# USB2CAN.net
KiCad netlist of a schematic drawn in Altium Designer
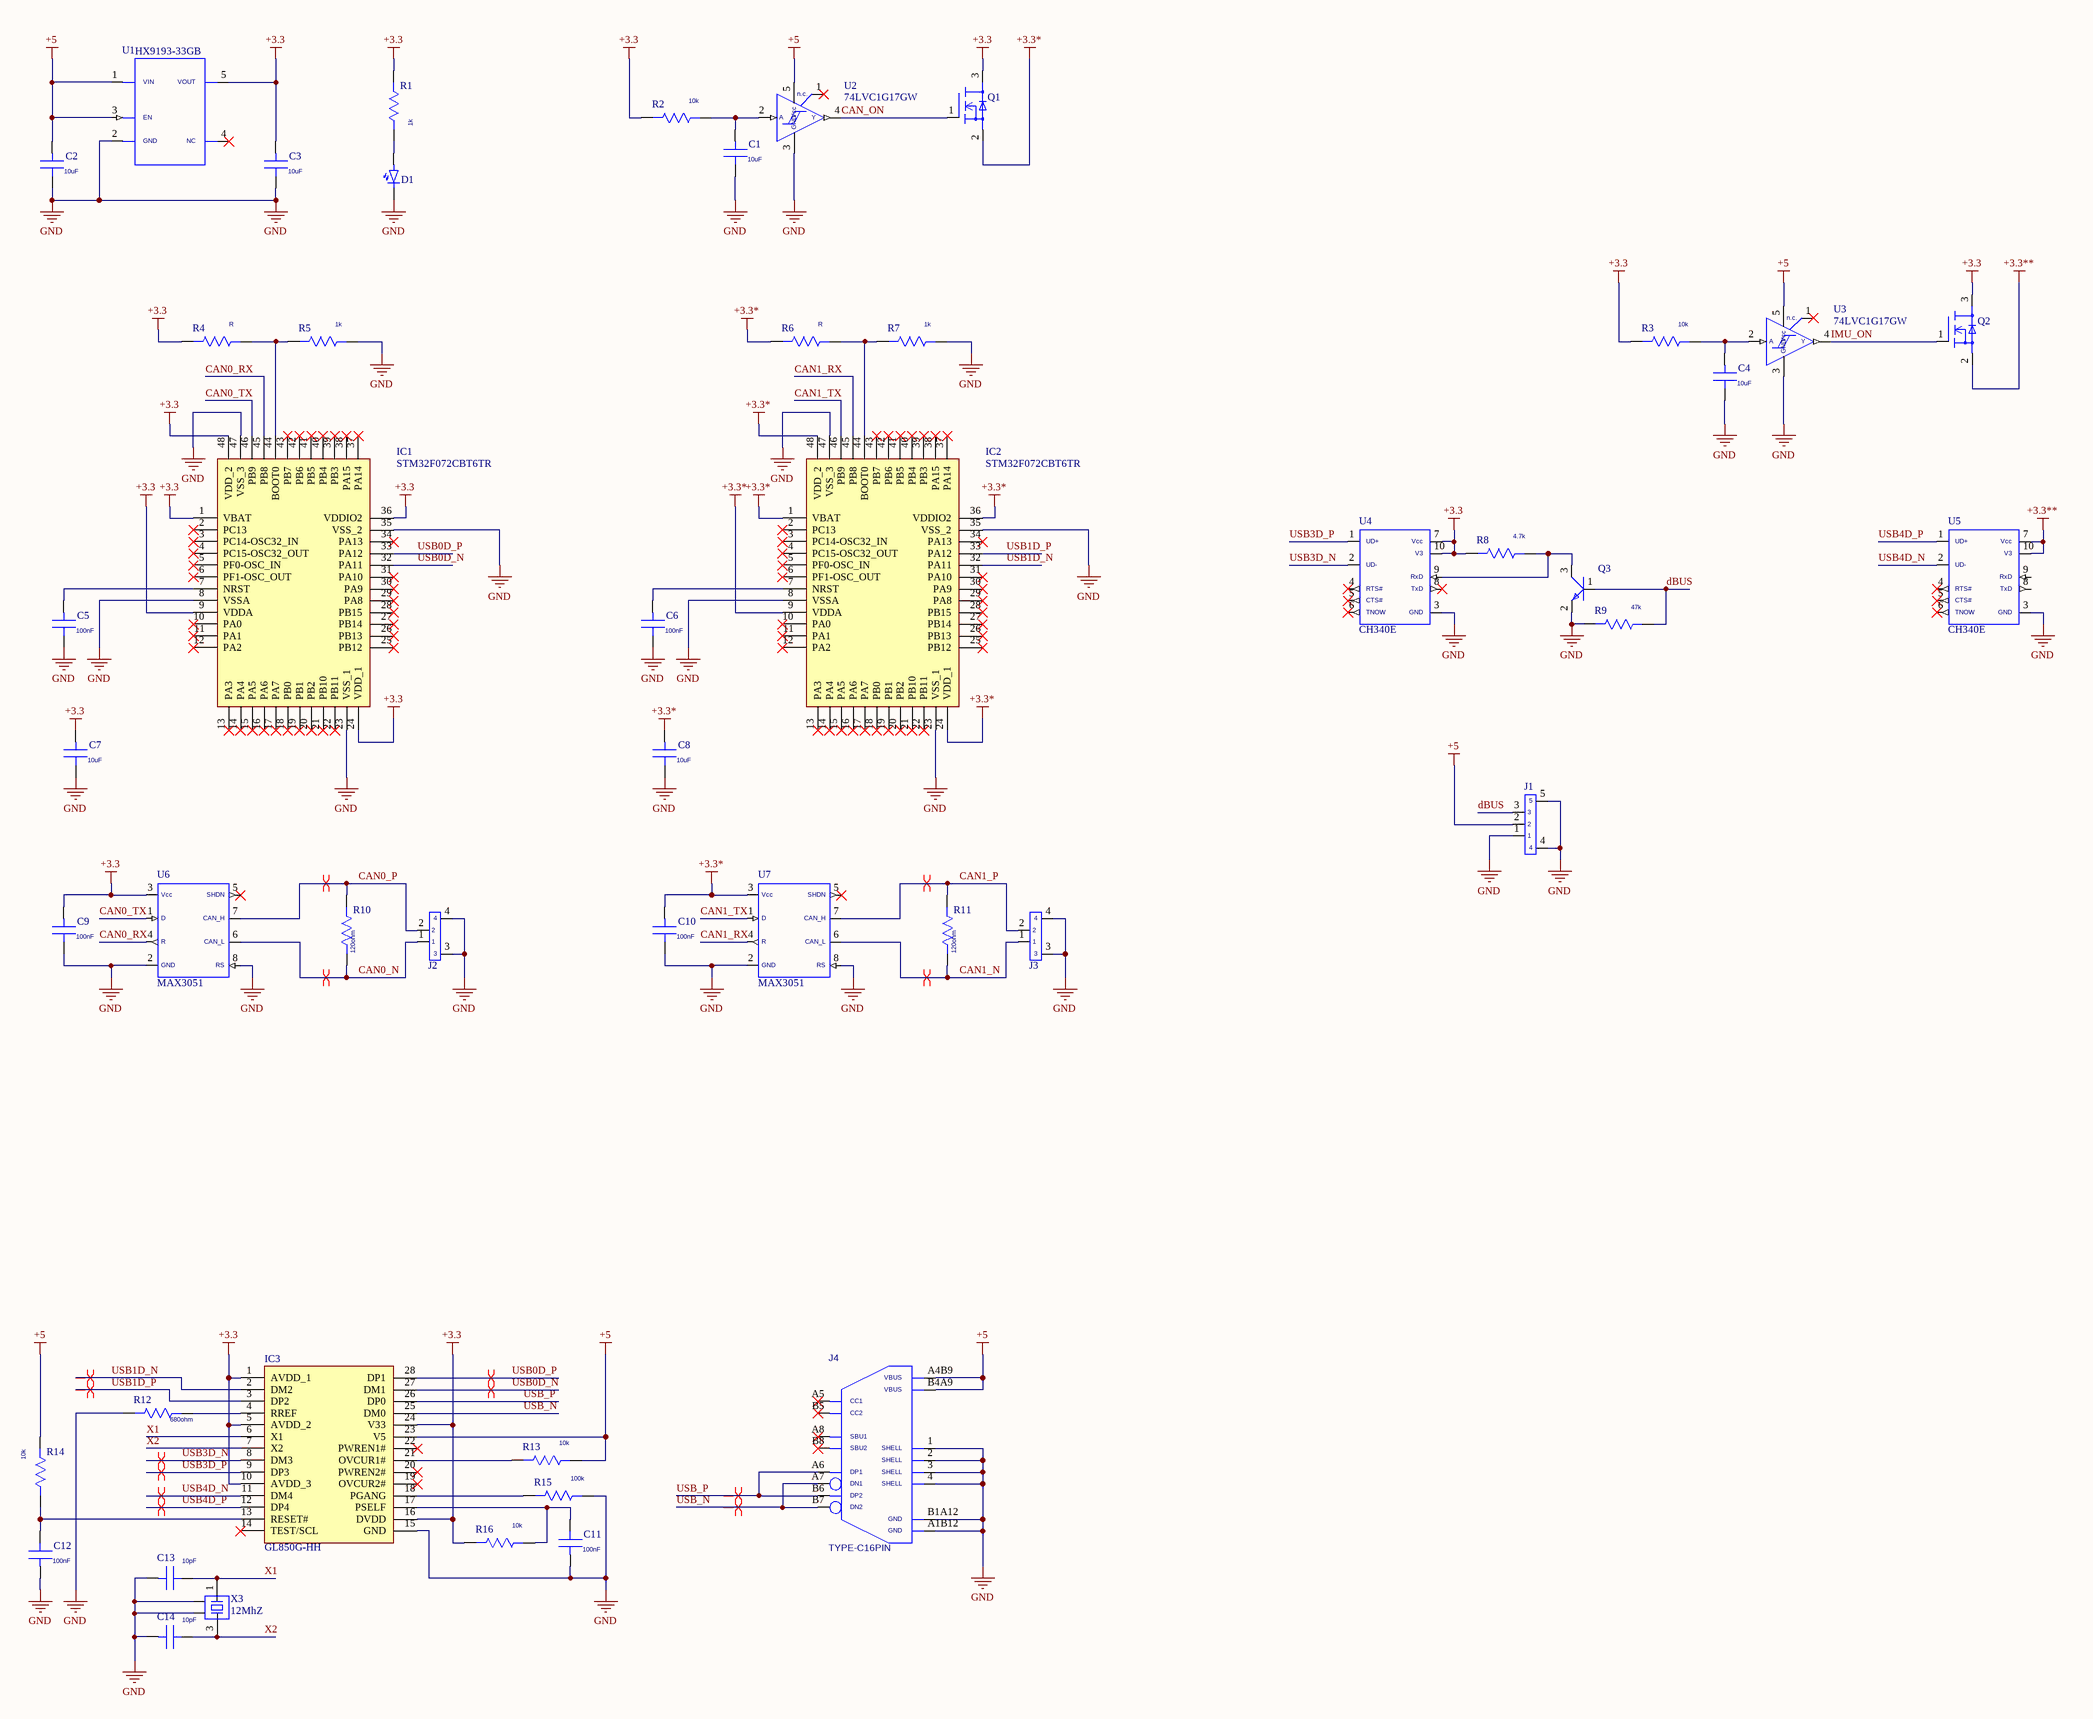
[diagram p0: USB2CAN.SchDoc]

(export (version "E")
  (design (tool "Eeschema 10.0.6"))
  (components
    (comp (ref "C1") (value "10uF") (footprint "0603C(M1608C)") (libsource (lib "ADlib @LAN") (part "C")))
    (comp (ref "C2") (value "10uF") (footprint "0603C(M1608C)") (libsource (lib "ADlib @LAN") (part "C")))
    (comp (ref "C3") (value "10uF") (footprint "0603C(M1608C)") (libsource (lib "ADlib @LAN") (part "C")))
    (comp (ref "C4") (value "10uF") (footprint "0603C(M1608C)") (libsource (lib "ADlib @LAN") (part "C")))
    (comp (ref "C5") (value "100nF") (footprint "0402C(M1005C)") (libsource (lib "ADlib @LAN") (part "C")))
    (comp (ref "C6") (value "100nF") (footprint "0402C(M1005C)") (libsource (lib "ADlib @LAN") (part "C")))
    (comp (ref "C7") (value "10uF") (footprint "0603C(M1608C)") (libsource (lib "ADlib @LAN") (part "C")))
    (comp (ref "C8") (value "10uF") (footprint "0603C(M1608C)") (libsource (lib "ADlib @LAN") (part "C")))
    (comp (ref "C9") (value "100nF") (footprint "0402C(M1005C)") (libsource (lib "ADlib @LAN") (part "C")))
    (comp (ref "C10") (value "100nF") (footprint "0402C(M1005C)") (libsource (lib "ADlib @LAN") (part "C")))
    (comp (ref "C11") (value "100nF") (footprint "0402C(M1005C)") (libsource (lib "ADlib @LAN") (part "C")))
    (comp (ref "C12") (value "100nF") (footprint "0402C(M1005C)") (libsource (lib "ADlib @LAN") (part "C")))
    (comp (ref "C13") (value "10pF") (footprint "0402C(M1005C)") (libsource (lib "ADlib @LAN") (part "C")))
    (comp (ref "C14") (value "10pF") (footprint "0402C(M1005C)") (libsource (lib "ADlib @LAN") (part "C")))
    (comp (ref "D1") (value "LED") (footprint "LED0603") (libsource (lib "ADlib @LAN") (part "LED")))
    (comp (ref "IC1")
      (value "STM32F072CBT6TR")
      (footprint "SamacSys:QFP50P900X900X160-48N")
      (description "Integrated Circuit")
      (fields
        (field (name "MOUSER PART NUMBER") "511-STM32F072CBT6TR")
        (field (name "RS PART NUMBER") "1923612")
      )
      (libsource (lib "*") (part "STM32F072CBT6TR"))
    )
    (comp (ref "IC2")
      (value "STM32F072CBT6TR")
      (footprint "SamacSys:QFP50P900X900X160-48N")
      (description "Integrated Circuit")
      (fields
        (field (name "MOUSER PART NUMBER") "511-STM32F072CBT6TR")
        (field (name "RS PART NUMBER") "1923612")
      )
      (libsource (lib "*") (part "STM32F072CBT6TR"))
    )
    (comp (ref "IC3")
      (value "GL850G-HH")
      (footprint "SamacSys:SOP65P780X200-28N")
      (description "Integrated Circuit")
      (libsource (lib "*") (part "GL850G-HH"))
    )
    (comp (ref "J1")
      (value "X1251WRS-03HF-LPSW")
      (footprint "GH1.25-3P")
      (libsource (lib "ADlib @LAN") (part "CON_GH1.25_3P"))
    )
    (comp (ref "J2")
      (value "X1251WRS-02HF-LPSW")
      (footprint "GH1.25-2P")
      (libsource (lib "ADlib @LAN") (part "CON_GH1.25_2P"))
    )
    (comp (ref "J3")
      (value "X1251WRS-02HF-LPSW")
      (footprint "GH1.25-2P")
      (libsource (lib "ADlib @LAN") (part "CON_GH1.25_2P"))
    )
    (comp (ref "J4")
      (value "TYPE-C16PIN")
      (footprint "Type-C 16P")
      (fields (field (name "BOM_SUPPLIER PART") "C393939") (field (name "CONTRIBUTOR") "LCSC"))
      (libsource (lib "ADlib @LAN") (part "CON_USB3#1"))
    )
    (comp (ref "Q1") (value "Q_FET_N") (footprint "SOT23") (libsource (lib "ADlib @LAN") (part "Q_FET_N")))
    (comp (ref "Q2") (value "Q_FET_N") (footprint "SOT23") (libsource (lib "ADlib @LAN") (part "Q_FET_N")))
    (comp (ref "Q3")
      (value "Q_NPN")
      (footprint "ADlib @LAN:SOT23")
      (libsource (lib "ADlib @LAN") (part "Q_NPN"))
    )
    (comp (ref "R1") (value "1k") (footprint "0402R") (libsource (lib "ADlib @LAN") (part "R")))
    (comp (ref "R2") (value "10k") (footprint "0402R") (libsource (lib "ADlib @LAN") (part "R")))
    (comp (ref "R3") (value "10k") (footprint "0402R") (libsource (lib "ADlib @LAN") (part "R")))
    (comp (ref "R4") (value "R") (footprint "0402R") (libsource (lib "ADlib @LAN") (part "R")))
    (comp (ref "R5") (value "1k") (footprint "0402R") (libsource (lib "ADlib @LAN") (part "R")))
    (comp (ref "R6") (value "R") (footprint "0402R") (libsource (lib "ADlib @LAN") (part "R")))
    (comp (ref "R7") (value "1k") (footprint "0402R") (libsource (lib "ADlib @LAN") (part "R")))
    (comp (ref "R8") (value "4.7k") (footprint "0402R") (libsource (lib "ADlib @LAN") (part "R")))
    (comp (ref "R9") (value "47k") (footprint "0402R") (libsource (lib "ADlib @LAN") (part "R")))
    (comp (ref "R10") (value "120ohm") (footprint "0402R") (libsource (lib "ADlib @LAN") (part "R")))
    (comp (ref "R11") (value "120ohm") (footprint "0402R") (libsource (lib "ADlib @LAN") (part "R")))
    (comp (ref "R12") (value "680ohm") (footprint "0402R") (libsource (lib "ADlib @LAN") (part "R")))
    (comp (ref "R13") (value "10k") (footprint "0402R") (libsource (lib "ADlib @LAN") (part "R")))
    (comp (ref "R14") (value "10k") (footprint "0402R") (libsource (lib "ADlib @LAN") (part "R")))
    (comp (ref "R15") (value "100k") (footprint "0402R") (libsource (lib "ADlib @LAN") (part "R")))
    (comp (ref "R16") (value "10k") (footprint "0402R") (libsource (lib "ADlib @LAN") (part "R")))
    (comp (ref "U1")
      (value "HX9193-33GB")
      (footprint "ADlib @LAN:SOT23_5")
      (libsource (lib "ADlib @LAN") (part "U_LDO"))
    )
    (comp (ref "U2")
      (value "74LVC1G17GW")
      (footprint "SOT353")
      (libsource (lib "ADlib @LAN") (part "U_Schmitt"))
    )
    (comp (ref "U3")
      (value "74LVC1G17GW")
      (footprint "SOT353")
      (libsource (lib "ADlib @LAN") (part "U_Schmitt"))
    )
    (comp (ref "U4")
      (value "CH340E")
      (footprint "ADlib @LAN:VSSOP10")
      (libsource (lib "ADlib @LAN") (part "U_UART_TRANS"))
    )
    (comp (ref "U5")
      (value "CH340E")
      (footprint "ADlib @LAN:VSSOP10")
      (libsource (lib "ADlib @LAN") (part "U_UART_TRANS"))
    )
    (comp (ref "U6")
      (value "MAX3051")
      (footprint "SOT23_8")
      (libsource (lib "ADlib @LAN") (part "U_CAN_TRANS#1"))
    )
    (comp (ref "U7")
      (value "MAX3051")
      (footprint "SOT23_8")
      (libsource (lib "ADlib @LAN") (part "U_CAN_TRANS#1"))
    )
    (comp (ref "X3")
      (value "12MhZ")
      (footprint "OSC 3225-4P")
      (description "4脚无源晶振")
      (libsource (lib "ADlib @LAN") (part "XTAL_4P"))
    )
  )
  (nets
    (net (code "1") (name "+3.3") (class "Default")
      (node (ref "C3") (pin "1") (pinfunction "1_1") (pintype "bidirectional"))
      (node (ref "C7") (pin "1") (pinfunction "1_1") (pintype "bidirectional"))
      (node (ref "C9") (pin "1") (pinfunction "1_1") (pintype "bidirectional"))
      (node (ref "IC1") (pin "1") (pinfunction "VBAT_1") (pintype "passive"))
      (node (ref "IC1") (pin "24") (pinfunction "VDD_1_24") (pintype "passive"))
      (node (ref "IC1") (pin "36") (pinfunction "VDDIO2_36") (pintype "passive"))
      (node (ref "IC1") (pin "48") (pinfunction "VDD_2_48") (pintype "passive"))
      (node (ref "IC1") (pin "9") (pinfunction "VDDA_9") (pintype "passive"))
      (node (ref "IC3") (pin "1") (pinfunction "AVDD_1_1") (pintype "passive"))
      (node (ref "IC3") (pin "10") (pinfunction "AVDD_3_10") (pintype "passive"))
      (node (ref "IC3") (pin "16") (pinfunction "DVDD_16") (pintype "passive"))
      (node (ref "IC3") (pin "24") (pinfunction "V33_24") (pintype "passive"))
      (node (ref "IC3") (pin "5") (pinfunction "AVDD_2_5") (pintype "passive"))
      (node (ref "Q1") (pin "3") (pinfunction "D_3") (pintype "bidirectional"))
      (node (ref "Q2") (pin "3") (pinfunction "D_3") (pintype "bidirectional"))
      (node (ref "R1") (pin "1") (pinfunction "1_1") (pintype "bidirectional"))
      (node (ref "R16") (pin "1") (pinfunction "1_1") (pintype "bidirectional"))
      (node (ref "R2") (pin "1") (pinfunction "1_1") (pintype "bidirectional"))
      (node (ref "R3") (pin "1") (pinfunction "1_1") (pintype "bidirectional"))
      (node (ref "R4") (pin "1") (pinfunction "1_1") (pintype "bidirectional"))
      (node (ref "R8") (pin "1") (pinfunction "1_1") (pintype "bidirectional"))
      (node (ref "U1") (pin "5") (pinfunction "VOUT_5") (pintype "power_in"))
      (node (ref "U4") (pin "10") (pinfunction "V3_10") (pintype "power_in"))
      (node (ref "U4") (pin "7") (pinfunction "Vcc_7") (pintype "power_in"))
      (node (ref "U6") (pin "3") (pinfunction "Vcc_3") (pintype "power_in"))
    )
    (net (code "2") (name "+3.3*") (class "Default")
      (node (ref "C10") (pin "1") (pinfunction "1_1") (pintype "bidirectional"))
      (node (ref "C8") (pin "1") (pinfunction "1_1") (pintype "bidirectional"))
      (node (ref "IC2") (pin "1") (pinfunction "VBAT_1") (pintype "passive"))
      (node (ref "IC2") (pin "24") (pinfunction "VDD_1_24") (pintype "passive"))
      (node (ref "IC2") (pin "36") (pinfunction "VDDIO2_36") (pintype "passive"))
      (node (ref "IC2") (pin "48") (pinfunction "VDD_2_48") (pintype "passive"))
      (node (ref "IC2") (pin "9") (pinfunction "VDDA_9") (pintype "passive"))
      (node (ref "Q1") (pin "2") (pinfunction "S_2") (pintype "bidirectional"))
      (node (ref "R6") (pin "1") (pinfunction "1_1") (pintype "bidirectional"))
      (node (ref "U7") (pin "3") (pinfunction "Vcc_3") (pintype "power_in"))
    )
    (net (code "3") (name "+3.3**") (class "Default")
      (node (ref "Q2") (pin "2") (pinfunction "S_2") (pintype "bidirectional"))
      (node (ref "U5") (pin "10") (pinfunction "V3_10") (pintype "power_in"))
      (node (ref "U5") (pin "7") (pinfunction "Vcc_7") (pintype "power_in"))
    )
    (net (code "4") (name "+5") (class "Default")
      (node (ref "C2") (pin "1") (pinfunction "1_1") (pintype "bidirectional"))
      (node (ref "IC3") (pin "23") (pinfunction "V5_23") (pintype "passive"))
      (node (ref "J1") (pin "2") (pinfunction "2_2") (pintype "bidirectional"))
      (node (ref "J4") (pin "A4B9") (pinfunction "VBUS_A4B9") (pintype "power_in"))
      (node (ref "J4") (pin "B4A9") (pinfunction "VBUS_B4A9") (pintype "power_in"))
      (node (ref "R13") (pin "2") (pinfunction "2_2") (pintype "bidirectional"))
      (node (ref "R14") (pin "1") (pinfunction "1_1") (pintype "bidirectional"))
      (node (ref "U1") (pin "1") (pinfunction "VIN_1") (pintype "power_in"))
      (node (ref "U1") (pin "3") (pinfunction "EN_3") (pintype "input"))
      (node (ref "U2") (pin "5") (pinfunction "Vcc_5") (pintype "power_in"))
      (node (ref "U3") (pin "5") (pinfunction "Vcc_5") (pintype "power_in"))
    )
    (net (code "5") (name "/CAN0_N") (class "Default")
      (node (ref "J2") (pin "1") (pinfunction "1_1") (pintype "bidirectional"))
      (node (ref "R10") (pin "2") (pinfunction "2_2") (pintype "bidirectional"))
      (node (ref "U6") (pin "6") (pinfunction "CAN_L_6") (pintype "bidirectional"))
    )
    (net (code "6") (name "/CAN0_P") (class "Default")
      (node (ref "J2") (pin "2") (pinfunction "2_2") (pintype "bidirectional"))
      (node (ref "R10") (pin "1") (pinfunction "1_1") (pintype "bidirectional"))
      (node (ref "U6") (pin "7") (pinfunction "CAN_H_7") (pintype "bidirectional"))
    )
    (net (code "7") (name "/CAN0_RX") (class "Default")
      (node (ref "IC1") (pin "45") (pinfunction "PB8_45") (pintype "passive"))
      (node (ref "U6") (pin "4") (pinfunction "R_4") (pintype "output"))
    )
    (net (code "8") (name "/CAN0_TX") (class "Default")
      (node (ref "IC1") (pin "46") (pinfunction "PB9_46") (pintype "passive"))
      (node (ref "U6") (pin "1") (pinfunction "D_1") (pintype "input"))
    )
    (net (code "9") (name "/CAN1_N") (class "Default")
      (node (ref "J3") (pin "1") (pinfunction "1_1") (pintype "bidirectional"))
      (node (ref "R11") (pin "2") (pinfunction "2_2") (pintype "bidirectional"))
      (node (ref "U7") (pin "6") (pinfunction "CAN_L_6") (pintype "bidirectional"))
    )
    (net (code "10") (name "/CAN1_P") (class "Default")
      (node (ref "J3") (pin "2") (pinfunction "2_2") (pintype "bidirectional"))
      (node (ref "R11") (pin "1") (pinfunction "1_1") (pintype "bidirectional"))
      (node (ref "U7") (pin "7") (pinfunction "CAN_H_7") (pintype "bidirectional"))
    )
    (net (code "11") (name "/CAN1_RX") (class "Default")
      (node (ref "IC2") (pin "45") (pinfunction "PB8_45") (pintype "passive"))
      (node (ref "U7") (pin "4") (pinfunction "R_4") (pintype "output"))
    )
    (net (code "12") (name "/CAN1_TX") (class "Default")
      (node (ref "IC2") (pin "46") (pinfunction "PB9_46") (pintype "passive"))
      (node (ref "U7") (pin "1") (pinfunction "D_1") (pintype "input"))
    )
    (net (code "13") (name "/CAN_ON") (class "Default")
      (node (ref "Q1") (pin "1") (pinfunction "G_1") (pintype "bidirectional"))
      (node (ref "U2") (pin "4") (pinfunction "Y_4") (pintype "output"))
    )
    (net (code "14") (name "/IMU_ON") (class "Default")
      (node (ref "Q2") (pin "1") (pinfunction "G_1") (pintype "bidirectional"))
      (node (ref "U3") (pin "4") (pinfunction "Y_4") (pintype "output"))
    )
    (net (code "15") (name "/USB0D_N") (class "Default")
      (node (ref "IC1") (pin "32") (pinfunction "PA11_32") (pintype "passive"))
      (node (ref "IC3") (pin "27") (pinfunction "DM1_27") (pintype "passive"))
    )
    (net (code "16") (name "/USB0D_P") (class "Default")
      (node (ref "IC1") (pin "33") (pinfunction "PA12_33") (pintype "passive"))
      (node (ref "IC3") (pin "28") (pinfunction "DP1_28") (pintype "passive"))
    )
    (net (code "17") (name "/USB1D_N") (class "Default")
      (node (ref "IC2") (pin "32") (pinfunction "PA11_32") (pintype "passive"))
      (node (ref "IC3") (pin "2") (pinfunction "DM2_2") (pintype "passive"))
    )
    (net (code "18") (name "/USB1D_P") (class "Default")
      (node (ref "IC2") (pin "33") (pinfunction "PA12_33") (pintype "passive"))
      (node (ref "IC3") (pin "3") (pinfunction "DP2_3") (pintype "passive"))
    )
    (net (code "19") (name "/USB3D_N") (class "Default")
      (node (ref "IC3") (pin "8") (pinfunction "DM3_8") (pintype "passive"))
      (node (ref "U4") (pin "2") (pinfunction "UD-_2") (pintype "bidirectional"))
    )
    (net (code "20") (name "/USB3D_P") (class "Default")
      (node (ref "IC3") (pin "9") (pinfunction "DP3_9") (pintype "passive"))
      (node (ref "U4") (pin "1") (pinfunction "UD+_1") (pintype "bidirectional"))
    )
    (net (code "21") (name "/USB4D_N") (class "Default")
      (node (ref "IC3") (pin "11") (pinfunction "DM4_11") (pintype "passive"))
      (node (ref "U5") (pin "2") (pinfunction "UD-_2") (pintype "bidirectional"))
    )
    (net (code "22") (name "/USB4D_P") (class "Default")
      (node (ref "IC3") (pin "12") (pinfunction "DP4_12") (pintype "passive"))
      (node (ref "U5") (pin "1") (pinfunction "UD+_1") (pintype "bidirectional"))
    )
    (net (code "23") (name "/USB_N") (class "Default")
      (node (ref "IC3") (pin "25") (pinfunction "DM0_25") (pintype "passive"))
      (node (ref "J4") (pin "A7") (pinfunction "DN1_A7") (pintype "bidirectional"))
      (node (ref "J4") (pin "B7") (pinfunction "DN2_B7") (pintype "bidirectional"))
    )
    (net (code "24") (name "/USB_P") (class "Default")
      (node (ref "IC3") (pin "26") (pinfunction "DP0_26") (pintype "passive"))
      (node (ref "J4") (pin "A6") (pinfunction "DP1_A6") (pintype "bidirectional"))
      (node (ref "J4") (pin "B6") (pinfunction "DP2_B6") (pintype "bidirectional"))
    )
    (net (code "25") (name "/X1") (class "Default")
      (node (ref "C13") (pin "2") (pinfunction "2_2") (pintype "bidirectional"))
      (node (ref "IC3") (pin "6") (pinfunction "X1_6") (pintype "passive"))
      (node (ref "X3") (pin "1") (pinfunction "1_1") (pintype "passive"))
    )
    (net (code "26") (name "/X2") (class "Default")
      (node (ref "C14") (pin "2") (pinfunction "2_2") (pintype "bidirectional"))
      (node (ref "IC3") (pin "7") (pinfunction "X2_7") (pintype "passive"))
      (node (ref "X3") (pin "3") (pinfunction "3_3") (pintype "passive"))
    )
    (net (code "27") (name "/dBUS") (class "Default")
      (node (ref "J1") (pin "3") (pinfunction "3_3") (pintype "bidirectional"))
      (node (ref "Q3") (pin "1") (pinfunction "B_1") (pintype "bidirectional"))
      (node (ref "R9") (pin "2") (pinfunction "2_2") (pintype "bidirectional"))
    )
    (net (code "28") (name "GND") (class "Default")
      (node (ref "C1") (pin "2") (pinfunction "2_2") (pintype "bidirectional"))
      (node (ref "C10") (pin "2") (pinfunction "2_2") (pintype "bidirectional"))
      (node (ref "C11") (pin "1") (pinfunction "1_1") (pintype "bidirectional"))
      (node (ref "C12") (pin "1") (pinfunction "1_1") (pintype "bidirectional"))
      (node (ref "C13") (pin "1") (pinfunction "1_1") (pintype "bidirectional"))
      (node (ref "C14") (pin "1") (pinfunction "1_1") (pintype "bidirectional"))
      (node (ref "C2") (pin "2") (pinfunction "2_2") (pintype "bidirectional"))
      (node (ref "C3") (pin "2") (pinfunction "2_2") (pintype "bidirectional"))
      (node (ref "C4") (pin "2") (pinfunction "2_2") (pintype "bidirectional"))
      (node (ref "C5") (pin "2") (pinfunction "2_2") (pintype "bidirectional"))
      (node (ref "C6") (pin "2") (pinfunction "2_2") (pintype "bidirectional"))
      (node (ref "C7") (pin "2") (pinfunction "2_2") (pintype "bidirectional"))
      (node (ref "C8") (pin "2") (pinfunction "2_2") (pintype "bidirectional"))
      (node (ref "C9") (pin "2") (pinfunction "2_2") (pintype "bidirectional"))
      (node (ref "D1") (pin "2") (pinfunction "2_2") (pintype "bidirectional"))
      (node (ref "IC1") (pin "23") (pinfunction "VSS_1_23") (pintype "passive"))
      (node (ref "IC1") (pin "35") (pinfunction "VSS_2_35") (pintype "passive"))
      (node (ref "IC1") (pin "47") (pinfunction "VSS_3_47") (pintype "passive"))
      (node (ref "IC1") (pin "8") (pinfunction "VSSA_8") (pintype "passive"))
      (node (ref "IC2") (pin "23") (pinfunction "VSS_1_23") (pintype "passive"))
      (node (ref "IC2") (pin "35") (pinfunction "VSS_2_35") (pintype "passive"))
      (node (ref "IC2") (pin "47") (pinfunction "VSS_3_47") (pintype "passive"))
      (node (ref "IC2") (pin "8") (pinfunction "VSSA_8") (pintype "passive"))
      (node (ref "IC3") (pin "15") (pinfunction "GND_15") (pintype "passive"))
      (node (ref "J1") (pin "1") (pinfunction "1_1") (pintype "bidirectional"))
      (node (ref "J1") (pin "4") (pinfunction "4_4") (pintype "passive"))
      (node (ref "J1") (pin "5") (pinfunction "5_5") (pintype "passive"))
      (node (ref "J2") (pin "3") (pinfunction "3_3") (pintype "power_in"))
      (node (ref "J2") (pin "4") (pinfunction "4_4") (pintype "power_in"))
      (node (ref "J3") (pin "3") (pinfunction "3_3") (pintype "power_in"))
      (node (ref "J3") (pin "4") (pinfunction "4_4") (pintype "power_in"))
      (node (ref "J4") (pin "1") (pinfunction "SHELL_1") (pintype "passive"))
      (node (ref "J4") (pin "2") (pinfunction "SHELL_2") (pintype "passive"))
      (node (ref "J4") (pin "3") (pinfunction "SHELL_3") (pintype "passive"))
      (node (ref "J4") (pin "4") (pinfunction "SHELL_4") (pintype "passive"))
      (node (ref "J4") (pin "A1B12") (pinfunction "GND_A1B12") (pintype "power_in"))
      (node (ref "J4") (pin "B1A12") (pinfunction "GND_B1A12") (pintype "power_in"))
      (node (ref "Q3") (pin "2") (pinfunction "E_2") (pintype "bidirectional"))
      (node (ref "R12") (pin "1") (pinfunction "1_1") (pintype "bidirectional"))
      (node (ref "R15") (pin "2") (pinfunction "2_2") (pintype "bidirectional"))
      (node (ref "R5") (pin "2") (pinfunction "2_2") (pintype "bidirectional"))
      (node (ref "R7") (pin "2") (pinfunction "2_2") (pintype "bidirectional"))
      (node (ref "R9") (pin "1") (pinfunction "1_1") (pintype "bidirectional"))
      (node (ref "U1") (pin "2") (pinfunction "GND_2") (pintype "power_in"))
      (node (ref "U2") (pin "3") (pinfunction "GND_3") (pintype "power_in"))
      (node (ref "U3") (pin "3") (pinfunction "GND_3") (pintype "power_in"))
      (node (ref "U4") (pin "3") (pinfunction "GND_3") (pintype "power_in"))
      (node (ref "U5") (pin "3") (pinfunction "GND_3") (pintype "power_in"))
      (node (ref "U6") (pin "2") (pinfunction "GND_2") (pintype "power_in"))
      (node (ref "U6") (pin "8") (pinfunction "RS_8") (pintype "input"))
      (node (ref "U7") (pin "2") (pinfunction "GND_2") (pintype "power_in"))
      (node (ref "U7") (pin "8") (pinfunction "RS_8") (pintype "input"))
      (node (ref "X3") (pin "2") (pinfunction "2_2") (pintype "passive"))
      (node (ref "X3") (pin "4") (pinfunction "4_4") (pintype "passive"))
    )
    (net (code "29") (name "Net-(D1-Pad1)") (class "Default")
      (node (ref "D1") (pin "1") (pinfunction "1_1") (pintype "bidirectional"))
      (node (ref "R1") (pin "2") (pinfunction "2_2") (pintype "bidirectional"))
    )
    (net (code "30") (name "Net-(IC1-BOOT0)") (class "Default")
      (node (ref "IC1") (pin "44") (pinfunction "BOOT0_44") (pintype "passive"))
      (node (ref "R4") (pin "2") (pinfunction "2_2") (pintype "bidirectional"))
      (node (ref "R5") (pin "1") (pinfunction "1_1") (pintype "bidirectional"))
    )
    (net (code "31") (name "Net-(IC1-NRST)") (class "Default")
      (node (ref "C5") (pin "1") (pinfunction "1_1") (pintype "bidirectional"))
      (node (ref "IC1") (pin "7") (pinfunction "NRST_7") (pintype "passive"))
    )
    (net (code "32") (name "Net-(IC2-BOOT0)") (class "Default")
      (node (ref "IC2") (pin "44") (pinfunction "BOOT0_44") (pintype "passive"))
      (node (ref "R6") (pin "2") (pinfunction "2_2") (pintype "bidirectional"))
      (node (ref "R7") (pin "1") (pinfunction "1_1") (pintype "bidirectional"))
    )
    (net (code "33") (name "Net-(IC2-NRST)") (class "Default")
      (node (ref "C6") (pin "1") (pinfunction "1_1") (pintype "bidirectional"))
      (node (ref "IC2") (pin "7") (pinfunction "NRST_7") (pintype "passive"))
    )
    (net (code "34") (name "Net-(IC3-OVCUR1#)") (class "Default")
      (node (ref "IC3") (pin "21") (pinfunction "OVCUR1#_21") (pintype "passive"))
      (node (ref "R13") (pin "1") (pinfunction "1_1") (pintype "bidirectional"))
    )
    (net (code "35") (name "Net-(IC3-PGANG)") (class "Default")
      (node (ref "IC3") (pin "18") (pinfunction "PGANG_18") (pintype "passive"))
      (node (ref "R15") (pin "1") (pinfunction "1_1") (pintype "bidirectional"))
    )
    (net (code "36") (name "Net-(IC3-PSELF)") (class "Default")
      (node (ref "C11") (pin "2") (pinfunction "2_2") (pintype "bidirectional"))
      (node (ref "IC3") (pin "17") (pinfunction "PSELF_17") (pintype "passive"))
      (node (ref "R16") (pin "2") (pinfunction "2_2") (pintype "bidirectional"))
    )
    (net (code "37") (name "Net-(IC3-RESET#)") (class "Default")
      (node (ref "C12") (pin "2") (pinfunction "2_2") (pintype "bidirectional"))
      (node (ref "IC3") (pin "13") (pinfunction "RESET#_13") (pintype "passive"))
      (node (ref "R14") (pin "2") (pinfunction "2_2") (pintype "bidirectional"))
    )
    (net (code "38") (name "Net-(IC3-RREF)") (class "Default")
      (node (ref "IC3") (pin "4") (pinfunction "RREF_4") (pintype "passive"))
      (node (ref "R12") (pin "2") (pinfunction "2_2") (pintype "bidirectional"))
    )
    (net (code "39") (name "Net-(Q3-C)") (class "Default")
      (node (ref "Q3") (pin "3") (pinfunction "C_3") (pintype "bidirectional"))
      (node (ref "R8") (pin "2") (pinfunction "2_2") (pintype "bidirectional"))
      (node (ref "U4") (pin "9") (pinfunction "RxD_9") (pintype "input"))
    )
    (net (code "40") (name "Net-(U2-A)") (class "Default")
      (node (ref "C1") (pin "1") (pinfunction "1_1") (pintype "bidirectional"))
      (node (ref "R2") (pin "2") (pinfunction "2_2") (pintype "bidirectional"))
      (node (ref "U2") (pin "2") (pinfunction "A_2") (pintype "input"))
    )
    (net (code "41") (name "Net-(U3-A)") (class "Default")
      (node (ref "C4") (pin "1") (pinfunction "1_1") (pintype "bidirectional"))
      (node (ref "R3") (pin "2") (pinfunction "2_2") (pintype "bidirectional"))
      (node (ref "U3") (pin "2") (pinfunction "A_2") (pintype "input"))
    )
    (net (code "42") (name "unconnected-(IC1-PA0-Pad10)") (class "Default")
      (node (ref "IC1") (pin "10") (pinfunction "PA0_10") (pintype "passive+no_connect"))
    )
    (net (code "43") (name "unconnected-(IC1-PA1-Pad11)") (class "Default")
      (node (ref "IC1") (pin "11") (pinfunction "PA1_11") (pintype "passive+no_connect"))
    )
    (net (code "44") (name "unconnected-(IC1-PA2-Pad12)") (class "Default")
      (node (ref "IC1") (pin "12") (pinfunction "PA2_12") (pintype "passive+no_connect"))
    )
    (net (code "45") (name "unconnected-(IC1-PA3-Pad13)") (class "Default")
      (node (ref "IC1") (pin "13") (pinfunction "PA3_13") (pintype "passive+no_connect"))
    )
    (net (code "46") (name "unconnected-(IC1-PA4-Pad14)") (class "Default")
      (node (ref "IC1") (pin "14") (pinfunction "PA4_14") (pintype "passive+no_connect"))
    )
    (net (code "47") (name "unconnected-(IC1-PA5-Pad15)") (class "Default")
      (node (ref "IC1") (pin "15") (pinfunction "PA5_15") (pintype "passive+no_connect"))
    )
    (net (code "48") (name "unconnected-(IC1-PA6-Pad16)") (class "Default")
      (node (ref "IC1") (pin "16") (pinfunction "PA6_16") (pintype "passive+no_connect"))
    )
    (net (code "49") (name "unconnected-(IC1-PA7-Pad17)") (class "Default")
      (node (ref "IC1") (pin "17") (pinfunction "PA7_17") (pintype "passive+no_connect"))
    )
    (net (code "50") (name "unconnected-(IC1-PA8-Pad29)") (class "Default")
      (node (ref "IC1") (pin "29") (pinfunction "PA8_29") (pintype "passive+no_connect"))
    )
    (net (code "51") (name "unconnected-(IC1-PA9-Pad30)") (class "Default")
      (node (ref "IC1") (pin "30") (pinfunction "PA9_30") (pintype "passive+no_connect"))
    )
    (net (code "52") (name "unconnected-(IC1-PA10-Pad31)") (class "Default")
      (node (ref "IC1") (pin "31") (pinfunction "PA10_31") (pintype "passive+no_connect"))
    )
    (net (code "53") (name "unconnected-(IC1-PA13-Pad34)") (class "Default")
      (node (ref "IC1") (pin "34") (pinfunction "PA13_34") (pintype "passive+no_connect"))
    )
    (net (code "54") (name "unconnected-(IC1-PA14-Pad37)") (class "Default")
      (node (ref "IC1") (pin "37") (pinfunction "PA14_37") (pintype "passive+no_connect"))
    )
    (net (code "55") (name "unconnected-(IC1-PA15-Pad38)") (class "Default")
      (node (ref "IC1") (pin "38") (pinfunction "PA15_38") (pintype "passive+no_connect"))
    )
    (net (code "56") (name "unconnected-(IC1-PB0-Pad18)") (class "Default")
      (node (ref "IC1") (pin "18") (pinfunction "PB0_18") (pintype "passive+no_connect"))
    )
    (net (code "57") (name "unconnected-(IC1-PB1-Pad19)") (class "Default")
      (node (ref "IC1") (pin "19") (pinfunction "PB1_19") (pintype "passive+no_connect"))
    )
    (net (code "58") (name "unconnected-(IC1-PB2-Pad20)") (class "Default")
      (node (ref "IC1") (pin "20") (pinfunction "PB2_20") (pintype "passive+no_connect"))
    )
    (net (code "59") (name "unconnected-(IC1-PB3-Pad39)") (class "Default")
      (node (ref "IC1") (pin "39") (pinfunction "PB3_39") (pintype "passive+no_connect"))
    )
    (net (code "60") (name "unconnected-(IC1-PB4-Pad40)") (class "Default")
      (node (ref "IC1") (pin "40") (pinfunction "PB4_40") (pintype "passive+no_connect"))
    )
    (net (code "61") (name "unconnected-(IC1-PB5-Pad41)") (class "Default")
      (node (ref "IC1") (pin "41") (pinfunction "PB5_41") (pintype "passive+no_connect"))
    )
    (net (code "62") (name "unconnected-(IC1-PB6-Pad42)") (class "Default")
      (node (ref "IC1") (pin "42") (pinfunction "PB6_42") (pintype "passive+no_connect"))
    )
    (net (code "63") (name "unconnected-(IC1-PB7-Pad43)") (class "Default")
      (node (ref "IC1") (pin "43") (pinfunction "PB7_43") (pintype "passive+no_connect"))
    )
    (net (code "64") (name "unconnected-(IC1-PB10-Pad21)") (class "Default")
      (node (ref "IC1") (pin "21") (pinfunction "PB10_21") (pintype "passive+no_connect"))
    )
    (net (code "65") (name "unconnected-(IC1-PB11-Pad22)") (class "Default")
      (node (ref "IC1") (pin "22") (pinfunction "PB11_22") (pintype "passive+no_connect"))
    )
    (net (code "66") (name "unconnected-(IC1-PB12-Pad25)") (class "Default")
      (node (ref "IC1") (pin "25") (pinfunction "PB12_25") (pintype "passive+no_connect"))
    )
    (net (code "67") (name "unconnected-(IC1-PB13-Pad26)") (class "Default")
      (node (ref "IC1") (pin "26") (pinfunction "PB13_26") (pintype "passive+no_connect"))
    )
    (net (code "68") (name "unconnected-(IC1-PB14-Pad27)") (class "Default")
      (node (ref "IC1") (pin "27") (pinfunction "PB14_27") (pintype "passive+no_connect"))
    )
    (net (code "69") (name "unconnected-(IC1-PB15-Pad28)") (class "Default")
      (node (ref "IC1") (pin "28") (pinfunction "PB15_28") (pintype "passive+no_connect"))
    )
    (net (code "70") (name "unconnected-(IC1-PC13-Pad2)") (class "Default")
      (node (ref "IC1") (pin "2") (pinfunction "PC13_2") (pintype "passive+no_connect"))
    )
    (net (code "71") (name "unconnected-(IC1-PC14-OSC32_IN-Pad3)") (class "Default")
      (node (ref "IC1") (pin "3") (pinfunction "PC14-OSC32_IN_3") (pintype "passive+no_connect"))
    )
    (net (code "72") (name "unconnected-(IC1-PC15-OSC32_OUT-Pad4)") (class "Default")
      (node (ref "IC1") (pin "4") (pinfunction "PC15-OSC32_OUT_4") (pintype "passive+no_connect"))
    )
    (net (code "73") (name "unconnected-(IC1-PF0-OSC_IN-Pad5)") (class "Default")
      (node (ref "IC1") (pin "5") (pinfunction "PF0-OSC_IN_5") (pintype "passive+no_connect"))
    )
    (net (code "74") (name "unconnected-(IC1-PF1-OSC_OUT-Pad6)") (class "Default")
      (node (ref "IC1") (pin "6") (pinfunction "PF1-OSC_OUT_6") (pintype "passive+no_connect"))
    )
    (net (code "75") (name "unconnected-(IC2-PA0-Pad10)") (class "Default")
      (node (ref "IC2") (pin "10") (pinfunction "PA0_10") (pintype "passive+no_connect"))
    )
    (net (code "76") (name "unconnected-(IC2-PA1-Pad11)") (class "Default")
      (node (ref "IC2") (pin "11") (pinfunction "PA1_11") (pintype "passive+no_connect"))
    )
    (net (code "77") (name "unconnected-(IC2-PA2-Pad12)") (class "Default")
      (node (ref "IC2") (pin "12") (pinfunction "PA2_12") (pintype "passive+no_connect"))
    )
    (net (code "78") (name "unconnected-(IC2-PA3-Pad13)") (class "Default")
      (node (ref "IC2") (pin "13") (pinfunction "PA3_13") (pintype "passive+no_connect"))
    )
    (net (code "79") (name "unconnected-(IC2-PA4-Pad14)") (class "Default")
      (node (ref "IC2") (pin "14") (pinfunction "PA4_14") (pintype "passive+no_connect"))
    )
    (net (code "80") (name "unconnected-(IC2-PA5-Pad15)") (class "Default")
      (node (ref "IC2") (pin "15") (pinfunction "PA5_15") (pintype "passive+no_connect"))
    )
    (net (code "81") (name "unconnected-(IC2-PA6-Pad16)") (class "Default")
      (node (ref "IC2") (pin "16") (pinfunction "PA6_16") (pintype "passive+no_connect"))
    )
    (net (code "82") (name "unconnected-(IC2-PA7-Pad17)") (class "Default")
      (node (ref "IC2") (pin "17") (pinfunction "PA7_17") (pintype "passive+no_connect"))
    )
    (net (code "83") (name "unconnected-(IC2-PA8-Pad29)") (class "Default")
      (node (ref "IC2") (pin "29") (pinfunction "PA8_29") (pintype "passive+no_connect"))
    )
    (net (code "84") (name "unconnected-(IC2-PA9-Pad30)") (class "Default")
      (node (ref "IC2") (pin "30") (pinfunction "PA9_30") (pintype "passive+no_connect"))
    )
    (net (code "85") (name "unconnected-(IC2-PA10-Pad31)") (class "Default")
      (node (ref "IC2") (pin "31") (pinfunction "PA10_31") (pintype "passive+no_connect"))
    )
    (net (code "86") (name "unconnected-(IC2-PA13-Pad34)") (class "Default")
      (node (ref "IC2") (pin "34") (pinfunction "PA13_34") (pintype "passive+no_connect"))
    )
    (net (code "87") (name "unconnected-(IC2-PA14-Pad37)") (class "Default")
      (node (ref "IC2") (pin "37") (pinfunction "PA14_37") (pintype "passive+no_connect"))
    )
    (net (code "88") (name "unconnected-(IC2-PA15-Pad38)") (class "Default")
      (node (ref "IC2") (pin "38") (pinfunction "PA15_38") (pintype "passive+no_connect"))
    )
    (net (code "89") (name "unconnected-(IC2-PB0-Pad18)") (class "Default")
      (node (ref "IC2") (pin "18") (pinfunction "PB0_18") (pintype "passive+no_connect"))
    )
    (net (code "90") (name "unconnected-(IC2-PB1-Pad19)") (class "Default")
      (node (ref "IC2") (pin "19") (pinfunction "PB1_19") (pintype "passive+no_connect"))
    )
    (net (code "91") (name "unconnected-(IC2-PB2-Pad20)") (class "Default")
      (node (ref "IC2") (pin "20") (pinfunction "PB2_20") (pintype "passive+no_connect"))
    )
    (net (code "92") (name "unconnected-(IC2-PB3-Pad39)") (class "Default")
      (node (ref "IC2") (pin "39") (pinfunction "PB3_39") (pintype "passive+no_connect"))
    )
    (net (code "93") (name "unconnected-(IC2-PB4-Pad40)") (class "Default")
      (node (ref "IC2") (pin "40") (pinfunction "PB4_40") (pintype "passive+no_connect"))
    )
    (net (code "94") (name "unconnected-(IC2-PB5-Pad41)") (class "Default")
      (node (ref "IC2") (pin "41") (pinfunction "PB5_41") (pintype "passive+no_connect"))
    )
    (net (code "95") (name "unconnected-(IC2-PB6-Pad42)") (class "Default")
      (node (ref "IC2") (pin "42") (pinfunction "PB6_42") (pintype "passive+no_connect"))
    )
    (net (code "96") (name "unconnected-(IC2-PB7-Pad43)") (class "Default")
      (node (ref "IC2") (pin "43") (pinfunction "PB7_43") (pintype "passive+no_connect"))
    )
    (net (code "97") (name "unconnected-(IC2-PB10-Pad21)") (class "Default")
      (node (ref "IC2") (pin "21") (pinfunction "PB10_21") (pintype "passive+no_connect"))
    )
    (net (code "98") (name "unconnected-(IC2-PB11-Pad22)") (class "Default")
      (node (ref "IC2") (pin "22") (pinfunction "PB11_22") (pintype "passive+no_connect"))
    )
    (net (code "99") (name "unconnected-(IC2-PB12-Pad25)") (class "Default")
      (node (ref "IC2") (pin "25") (pinfunction "PB12_25") (pintype "passive+no_connect"))
    )
    (net (code "100") (name "unconnected-(IC2-PB13-Pad26)") (class "Default")
      (node (ref "IC2") (pin "26") (pinfunction "PB13_26") (pintype "passive+no_connect"))
    )
    (net (code "101") (name "unconnected-(IC2-PB14-Pad27)") (class "Default")
      (node (ref "IC2") (pin "27") (pinfunction "PB14_27") (pintype "passive+no_connect"))
    )
    (net (code "102") (name "unconnected-(IC2-PB15-Pad28)") (class "Default")
      (node (ref "IC2") (pin "28") (pinfunction "PB15_28") (pintype "passive+no_connect"))
    )
    (net (code "103") (name "unconnected-(IC2-PC13-Pad2)") (class "Default")
      (node (ref "IC2") (pin "2") (pinfunction "PC13_2") (pintype "passive+no_connect"))
    )
    (net (code "104") (name "unconnected-(IC2-PC14-OSC32_IN-Pad3)") (class "Default")
      (node (ref "IC2") (pin "3") (pinfunction "PC14-OSC32_IN_3") (pintype "passive+no_connect"))
    )
    (net (code "105") (name "unconnected-(IC2-PC15-OSC32_OUT-Pad4)") (class "Default")
      (node (ref "IC2") (pin "4") (pinfunction "PC15-OSC32_OUT_4") (pintype "passive+no_connect"))
    )
    (net (code "106") (name "unconnected-(IC2-PF0-OSC_IN-Pad5)") (class "Default")
      (node (ref "IC2") (pin "5") (pinfunction "PF0-OSC_IN_5") (pintype "passive+no_connect"))
    )
    (net (code "107") (name "unconnected-(IC2-PF1-OSC_OUT-Pad6)") (class "Default")
      (node (ref "IC2") (pin "6") (pinfunction "PF1-OSC_OUT_6") (pintype "passive+no_connect"))
    )
    (net (code "108") (name "unconnected-(IC3-OVCUR2#-Pad19)") (class "Default")
      (node (ref "IC3") (pin "19") (pinfunction "OVCUR2#_19") (pintype "passive+no_connect"))
    )
    (net (code "109") (name "unconnected-(IC3-PWREN1#-Pad22)") (class "Default")
      (node (ref "IC3") (pin "22") (pinfunction "PWREN1#_22") (pintype "passive+no_connect"))
    )
    (net (code "110") (name "unconnected-(IC3-PWREN2#-Pad20)") (class "Default")
      (node (ref "IC3") (pin "20") (pinfunction "PWREN2#_20") (pintype "passive+no_connect"))
    )
    (net (code "111") (name "unconnected-(IC3-TEST{slash}SCL-Pad14)") (class "Default")
      (node (ref "IC3") (pin "14") (pinfunction "TEST/SCL_14") (pintype "passive+no_connect"))
    )
    (net (code "112") (name "unconnected-(J4-CC1-PadA5)") (class "Default")
      (node (ref "J4") (pin "A5") (pinfunction "CC1_A5") (pintype "bidirectional+no_connect"))
    )
    (net (code "113") (name "unconnected-(J4-CC2-PadB5)") (class "Default")
      (node (ref "J4") (pin "B5") (pinfunction "CC2_B5") (pintype "bidirectional+no_connect"))
    )
    (net (code "114") (name "unconnected-(J4-SBU1-PadA8)") (class "Default")
      (node (ref "J4") (pin "A8") (pinfunction "SBU1_A8") (pintype "bidirectional+no_connect"))
    )
    (net (code "115") (name "unconnected-(J4-SBU2-PadB8)") (class "Default")
      (node (ref "J4") (pin "B8") (pinfunction "SBU2_B8") (pintype "bidirectional+no_connect"))
    )
    (net (code "116") (name "unconnected-(U1-NC-Pad4)") (class "Default")
      (node (ref "U1") (pin "4") (pinfunction "NC_4") (pintype "passive+no_connect"))
    )
    (net (code "117") (name "unconnected-(U2-n.c.-Pad1)") (class "Default")
      (node (ref "U2") (pin "1") (pinfunction "n.c._1") (pintype "passive+no_connect"))
    )
    (net (code "118") (name "unconnected-(U3-n.c.-Pad1)") (class "Default")
      (node (ref "U3") (pin "1") (pinfunction "n.c._1") (pintype "passive+no_connect"))
    )
    (net (code "119") (name "unconnected-(U4-CTS#-Pad5)") (class "Default")
      (node (ref "U4") (pin "5") (pinfunction "CTS#_5") (pintype "output+no_connect"))
    )
    (net (code "120") (name "unconnected-(U4-RTS#-Pad4)") (class "Default")
      (node (ref "U4") (pin "4") (pinfunction "RTS#_4") (pintype "output+no_connect"))
    )
    (net (code "121") (name "unconnected-(U4-TNOW-Pad6)") (class "Default")
      (node (ref "U4") (pin "6") (pinfunction "TNOW_6") (pintype "output+no_connect"))
    )
    (net (code "122") (name "unconnected-(U4-TxD-Pad8)") (class "Default")
      (node (ref "U4") (pin "8") (pinfunction "TxD_8") (pintype "output+no_connect"))
    )
    (net (code "123") (name "unconnected-(U5-CTS#-Pad5)") (class "Default")
      (node (ref "U5") (pin "5") (pinfunction "CTS#_5") (pintype "output+no_connect"))
    )
    (net (code "124") (name "unconnected-(U5-RTS#-Pad4)") (class "Default")
      (node (ref "U5") (pin "4") (pinfunction "RTS#_4") (pintype "output+no_connect"))
    )
    (net (code "125") (name "unconnected-(U5-RxD-Pad9)") (class "Default")
      (node (ref "U5") (pin "9") (pinfunction "RxD_9") (pintype "input"))
    )
    (net (code "126") (name "unconnected-(U5-TNOW-Pad6)") (class "Default")
      (node (ref "U5") (pin "6") (pinfunction "TNOW_6") (pintype "output+no_connect"))
    )
    (net (code "127") (name "unconnected-(U5-TxD-Pad8)") (class "Default")
      (node (ref "U5") (pin "8") (pinfunction "TxD_8") (pintype "output"))
    )
    (net (code "128") (name "unconnected-(U6-SHDN-Pad5)") (class "Default")
      (node (ref "U6") (pin "5") (pinfunction "SHDN_5") (pintype "output+no_connect"))
    )
    (net (code "129") (name "unconnected-(U7-SHDN-Pad5)") (class "Default")
      (node (ref "U7") (pin "5") (pinfunction "SHDN_5") (pintype "output+no_connect"))
    )
  )
)
